# 6.net
KiCad netlist of a schematic drawn in Altium Designer
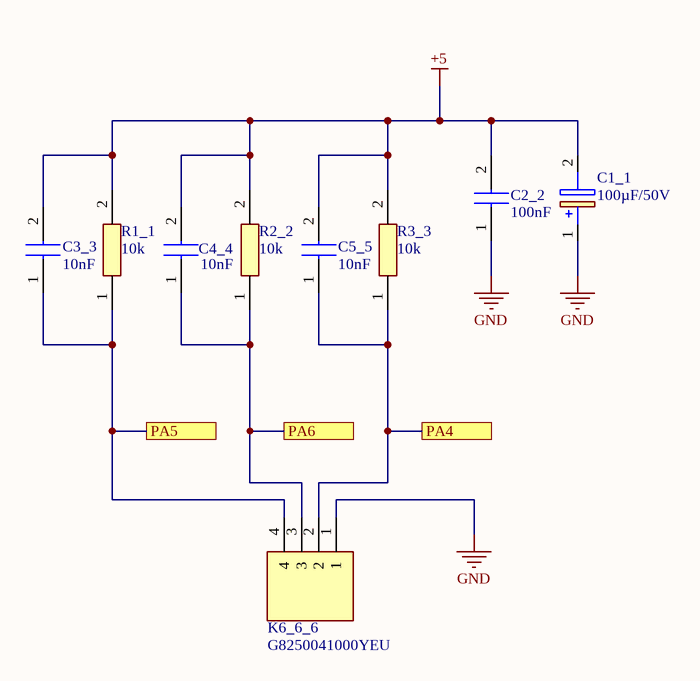
[diagram p0: 6.SchDoc]

(export (version "E")
  (design (tool "Eeschema 10.0.6"))
  (components
    (comp (ref "C1_1")
      (value "100µF/50V")
      (footprint "CAPPRD350W60D800H1250")
      (description "Capacitor Polarised")
      (fields (field (name "MANUFACTURER_PART_NUMBER") "ESK107M050AG3EA"))
      (libsource (lib "Condensator_100µF_V2") (part "ESK107M050AG3EA"))
    )
    (comp (ref "C2_2")
      (value "100nF")
      (footprint "0805")
      (description "Capacitor")
      (fields (field (name "MANUFACTURER_PART_NUMBER") "C0805C301G5GACTU"))
      (libsource (lib "Condensator_0805") (part "C0805C301G5GACTU"))
    )
    (comp (ref "C3_3")
      (value "10nF")
      (footprint "0805")
      (description "Capacitor")
      (fields (field (name "MANUFACTURER_PART_NUMBER") "C0805C301G5GACTU"))
      (libsource (lib "Condensator_0805") (part "C0805C301G5GACTU"))
    )
    (comp (ref "C4_4")
      (value "10nF")
      (footprint "0805")
      (description "Capacitor")
      (fields (field (name "MANUFACTURER_PART_NUMBER") "C0805C301G5GACTU"))
      (libsource (lib "Condensator_0805") (part "C0805C301G5GACTU"))
    )
    (comp (ref "C5_5")
      (value "10nF")
      (footprint "0805")
      (description "Capacitor")
      (fields (field (name "MANUFACTURER_PART_NUMBER") "C0805C301G5GACTU"))
      (libsource (lib "Condensator_0805") (part "C0805C301G5GACTU"))
    )
    (comp (ref "K6_6_6")
      (value "G8250041000YEU")
      (footprint "G8250041000YEU")
      (description "Connector")
      (libsource (lib "K6") (part "G8250041000YEU"))
    )
    (comp (ref "R1_1")
      (value "10k")
      (footprint "0805")
      (description "Resistor")
      (fields (field (name "MANUFACTURER_PART_NUMBER") "CFN0805-FZ-R030ELF"))
      (libsource (lib "Weerstand_0805") (part "CFN0805-FZ-R030ELF"))
    )
    (comp (ref "R2_2")
      (value "10k")
      (footprint "0805")
      (description "Resistor")
      (fields (field (name "MANUFACTURER_PART_NUMBER") "CFN0805-FZ-R030ELF"))
      (libsource (lib "Weerstand_0805") (part "CFN0805-FZ-R030ELF"))
    )
    (comp (ref "R3_3")
      (value "10k")
      (footprint "0805")
      (description "Resistor")
      (fields (field (name "MANUFACTURER_PART_NUMBER") "CFN0805-FZ-R030ELF"))
      (libsource (lib "Weerstand_0805") (part "CFN0805-FZ-R030ELF"))
    )
  )
  (nets
    (net (code "1") (name "+5") (class "Default")
      (node (ref "C1_1") (pin "2") (pinfunction "-_2") (pintype "passive"))
      (node (ref "C2_2") (pin "2") (pinfunction "2_2") (pintype "passive"))
      (node (ref "C3_3") (pin "2") (pinfunction "2_2") (pintype "passive"))
      (node (ref "C4_4") (pin "2") (pinfunction "2_2") (pintype "passive"))
      (node (ref "C5_5") (pin "2") (pinfunction "2_2") (pintype "passive"))
      (node (ref "R1_1") (pin "2") (pinfunction "2_2") (pintype "passive"))
      (node (ref "R2_2") (pin "2") (pinfunction "2_2") (pintype "passive"))
      (node (ref "R3_3") (pin "2") (pinfunction "2_2") (pintype "passive"))
    )
    (net (code "2") (name "/PA4") (class "Default")
      (node (ref "C5_5") (pin "1") (pinfunction "1_1") (pintype "passive"))
      (node (ref "K6_6_6") (pin "2") (pinfunction "2_2") (pintype "passive"))
      (node (ref "R3_3") (pin "1") (pinfunction "1_1") (pintype "passive"))
    )
    (net (code "3") (name "/PA5") (class "Default")
      (node (ref "C3_3") (pin "1") (pinfunction "1_1") (pintype "passive"))
      (node (ref "K6_6_6") (pin "4") (pinfunction "4_4") (pintype "passive"))
      (node (ref "R1_1") (pin "1") (pinfunction "1_1") (pintype "passive"))
    )
    (net (code "4") (name "/PA6") (class "Default")
      (node (ref "C4_4") (pin "1") (pinfunction "1_1") (pintype "passive"))
      (node (ref "K6_6_6") (pin "3") (pinfunction "3_3") (pintype "passive"))
      (node (ref "R2_2") (pin "1") (pinfunction "1_1") (pintype "passive"))
    )
    (net (code "5") (name "GND") (class "Default")
      (node (ref "C1_1") (pin "1") (pinfunction "+_1") (pintype "passive"))
      (node (ref "C2_2") (pin "1") (pinfunction "1_1") (pintype "passive"))
      (node (ref "K6_6_6") (pin "1") (pinfunction "1_1") (pintype "passive"))
    )
  )
)
